# HeightRuleRoom1_9mm.net
KiCad netlist of a schematic drawn in Altium Designer
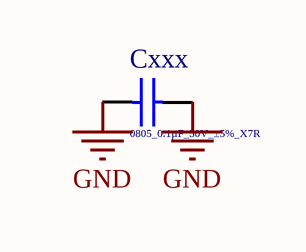
[diagram p0: HeightRuleRoom1.9mm.SchDoc]

(export (version "E")
  (design (tool "Eeschema 10.0.6"))
  (components
    (comp (ref "Cxxx")
      (value "0805_0.1µF_50V_±5%_X7R")
      (footprint "CAPC2012X140N")
      (description "CAP CER 0.1UF 50V 5% X7R 0805")
      (fields (field (name "PART NUMBER") "08055C104JAT2A") (field (name "MANUFACTURER") "AVX Corporation"))
      (libsource (lib "Capacitors") (part "Capacitor"))
    )
  )
  (nets
    (net (code "1") (name "GND") (class "Default")
      (node (ref "Cxxx") (pin "1") (pinfunction "1_1") (pintype "passive"))
      (node (ref "Cxxx") (pin "2") (pinfunction "2_2") (pintype "passive"))
    )
  )
)
